# CiroSonda_V1.net
KiCad netlist of a schematic drawn in EAGLE
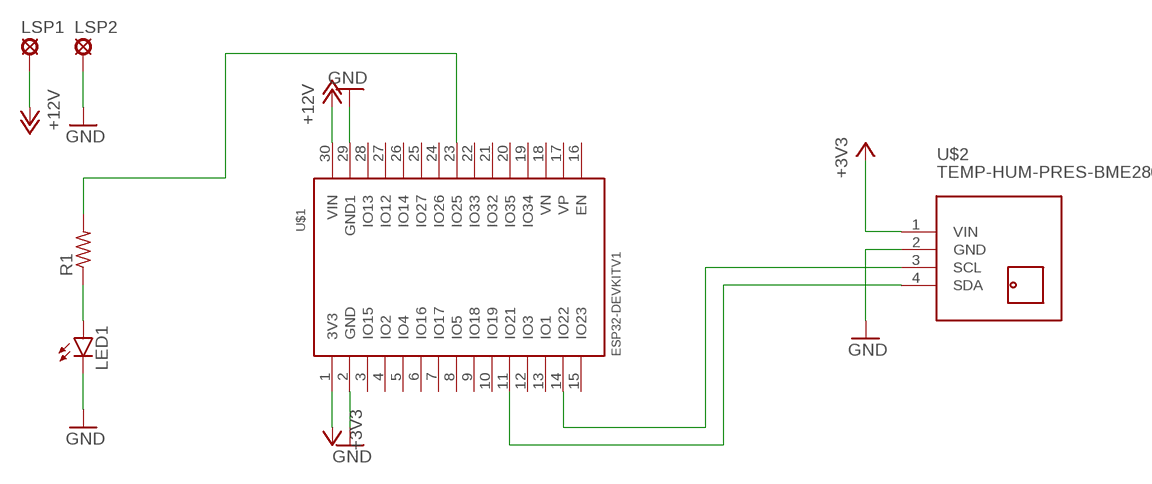
[diagram p0: schematic, sheet 1]

(export (version "E")
  (design (tool "Eeschema 10.0.6"))
  (components
    (comp (ref "LED1")
      (value "LED5MM")
      (footprint "eagle-import:LED5MM")
      (libsource (lib "eagle-import") (part "LED5MM"))
    )
    (comp (ref "LSP1")
      (value "LSP11")
      (footprint "eagle-import:LSP11")
      (libsource (lib "eagle-import") (part "LSP11"))
    )
    (comp (ref "LSP2")
      (value "LSP11")
      (footprint "eagle-import:LSP11")
      (libsource (lib "eagle-import") (part "LSP11"))
    )
    (comp (ref "R1")
      (value "R-US_0204/7")
      (footprint "eagle-import:0204_7")
      (libsource (lib "eagle-import") (part "R-US_0204/7"))
    )
    (comp (ref "U$1")
      (value "ESP32DEVKITV1")
      (footprint "eagle-import:ESP32-DEVKITV1")
      (libsource (lib "eagle-import") (part "ESP32DEVKITV1"))
    )
    (comp (ref "U$2")
      (value "TEMP-HUM-PRES-BME280")
      (footprint "eagle-import:TEMP-HUM-PRES-BME280")
      (libsource (lib "eagle-import") (part "TEMP-HUM-PRES-BME280"))
    )
  )
  (nets
    (net (code "1") (name "+3V3") (class "Default")
      (node (ref "U$1") (pin "1") (pinfunction "3V3_1") (pintype "bidirectional"))
      (node (ref "U$2") (pin "1") (pinfunction "VIN_1") (pintype "power_in"))
    )
    (net (code "2") (name "+12V") (class "Default")
      (node (ref "LSP1") (pin "MP") (pinfunction "MP_MP") (pintype "passive"))
      (node (ref "U$1") (pin "30") (pinfunction "VIN_30") (pintype "bidirectional"))
    )
    (net (code "3") (name "GND") (class "Default")
      (node (ref "LED1") (pin "K") (pinfunction "C_K") (pintype "passive"))
      (node (ref "LSP2") (pin "MP") (pinfunction "MP_MP") (pintype "passive"))
      (node (ref "U$1") (pin "2") (pinfunction "GND_2") (pintype "bidirectional"))
      (node (ref "U$1") (pin "29") (pinfunction "GND1_29") (pintype "bidirectional"))
      (node (ref "U$2") (pin "2") (pinfunction "GND_2") (pintype "power_in"))
    )
    (net (code "4") (name "Net-(LED1-PadA)") (class "Default")
      (node (ref "LED1") (pin "A") (pinfunction "A_A") (pintype "passive"))
      (node (ref "R1") (pin "1") (pinfunction "1_1") (pintype "passive"))
    )
    (net (code "5") (name "Net-(U$1-IO21)") (class "Default")
      (node (ref "U$1") (pin "11") (pinfunction "IO21_11") (pintype "bidirectional"))
      (node (ref "U$2") (pin "4") (pinfunction "SDA_4") (pintype "bidirectional"))
    )
    (net (code "6") (name "Net-(U$1-IO22)") (class "Default")
      (node (ref "U$1") (pin "14") (pinfunction "IO22_14") (pintype "bidirectional"))
      (node (ref "U$2") (pin "3") (pinfunction "SCL_3") (pintype "bidirectional"))
    )
    (net (code "7") (name "Net-(U$1-IO25)") (class "Default")
      (node (ref "R1") (pin "2") (pinfunction "2_2") (pintype "passive"))
      (node (ref "U$1") (pin "23") (pinfunction "IO25_23") (pintype "bidirectional"))
    )
    (net (code "8") (name "unconnected-(U$1-EN-Pad16)") (class "Default")
      (node (ref "U$1") (pin "16") (pinfunction "EN_16") (pintype "bidirectional"))
    )
    (net (code "9") (name "unconnected-(U$1-IO1-Pad13)") (class "Default")
      (node (ref "U$1") (pin "13") (pinfunction "IO1_13") (pintype "bidirectional"))
    )
    (net (code "10") (name "unconnected-(U$1-IO2-Pad4)") (class "Default")
      (node (ref "U$1") (pin "4") (pinfunction "IO2_4") (pintype "bidirectional"))
    )
    (net (code "11") (name "unconnected-(U$1-IO3-Pad12)") (class "Default")
      (node (ref "U$1") (pin "12") (pinfunction "IO3_12") (pintype "bidirectional"))
    )
    (net (code "12") (name "unconnected-(U$1-IO4-Pad5)") (class "Default")
      (node (ref "U$1") (pin "5") (pinfunction "IO4_5") (pintype "bidirectional"))
    )
    (net (code "13") (name "unconnected-(U$1-IO5-Pad8)") (class "Default")
      (node (ref "U$1") (pin "8") (pinfunction "IO5_8") (pintype "bidirectional"))
    )
    (net (code "14") (name "unconnected-(U$1-IO12-Pad27)") (class "Default")
      (node (ref "U$1") (pin "27") (pinfunction "IO12_27") (pintype "bidirectional"))
    )
    (net (code "15") (name "unconnected-(U$1-IO13-Pad28)") (class "Default")
      (node (ref "U$1") (pin "28") (pinfunction "IO13_28") (pintype "bidirectional"))
    )
    (net (code "16") (name "unconnected-(U$1-IO14-Pad26)") (class "Default")
      (node (ref "U$1") (pin "26") (pinfunction "IO14_26") (pintype "bidirectional"))
    )
    (net (code "17") (name "unconnected-(U$1-IO15-Pad3)") (class "Default")
      (node (ref "U$1") (pin "3") (pinfunction "IO15_3") (pintype "bidirectional"))
    )
    (net (code "18") (name "unconnected-(U$1-IO16-Pad6)") (class "Default")
      (node (ref "U$1") (pin "6") (pinfunction "IO16_6") (pintype "bidirectional"))
    )
    (net (code "19") (name "unconnected-(U$1-IO17-Pad7)") (class "Default")
      (node (ref "U$1") (pin "7") (pinfunction "IO17_7") (pintype "bidirectional"))
    )
    (net (code "20") (name "unconnected-(U$1-IO18-Pad9)") (class "Default")
      (node (ref "U$1") (pin "9") (pinfunction "IO18_9") (pintype "bidirectional"))
    )
    (net (code "21") (name "unconnected-(U$1-IO19-Pad10)") (class "Default")
      (node (ref "U$1") (pin "10") (pinfunction "IO19_10") (pintype "bidirectional"))
    )
    (net (code "22") (name "unconnected-(U$1-IO23-Pad15)") (class "Default")
      (node (ref "U$1") (pin "15") (pinfunction "IO23_15") (pintype "bidirectional"))
    )
    (net (code "23") (name "unconnected-(U$1-IO26-Pad24)") (class "Default")
      (node (ref "U$1") (pin "24") (pinfunction "IO26_24") (pintype "bidirectional"))
    )
    (net (code "24") (name "unconnected-(U$1-IO27-Pad25)") (class "Default")
      (node (ref "U$1") (pin "25") (pinfunction "IO27_25") (pintype "bidirectional"))
    )
    (net (code "25") (name "unconnected-(U$1-IO32-Pad21)") (class "Default")
      (node (ref "U$1") (pin "21") (pinfunction "IO32_21") (pintype "bidirectional"))
    )
    (net (code "26") (name "unconnected-(U$1-IO33-Pad22)") (class "Default")
      (node (ref "U$1") (pin "22") (pinfunction "IO33_22") (pintype "bidirectional"))
    )
    (net (code "27") (name "unconnected-(U$1-IO34-Pad19)") (class "Default")
      (node (ref "U$1") (pin "19") (pinfunction "IO34_19") (pintype "bidirectional"))
    )
    (net (code "28") (name "unconnected-(U$1-IO35-Pad20)") (class "Default")
      (node (ref "U$1") (pin "20") (pinfunction "IO35_20") (pintype "bidirectional"))
    )
    (net (code "29") (name "unconnected-(U$1-VN-Pad18)") (class "Default")
      (node (ref "U$1") (pin "18") (pinfunction "VN_18") (pintype "bidirectional"))
    )
    (net (code "30") (name "unconnected-(U$1-VP-Pad17)") (class "Default")
      (node (ref "U$1") (pin "17") (pinfunction "VP_17") (pintype "bidirectional"))
    )
  )
)
